# lumiere_ctrl_shematic.net
KiCad netlist of a schematic drawn in Altium Designer
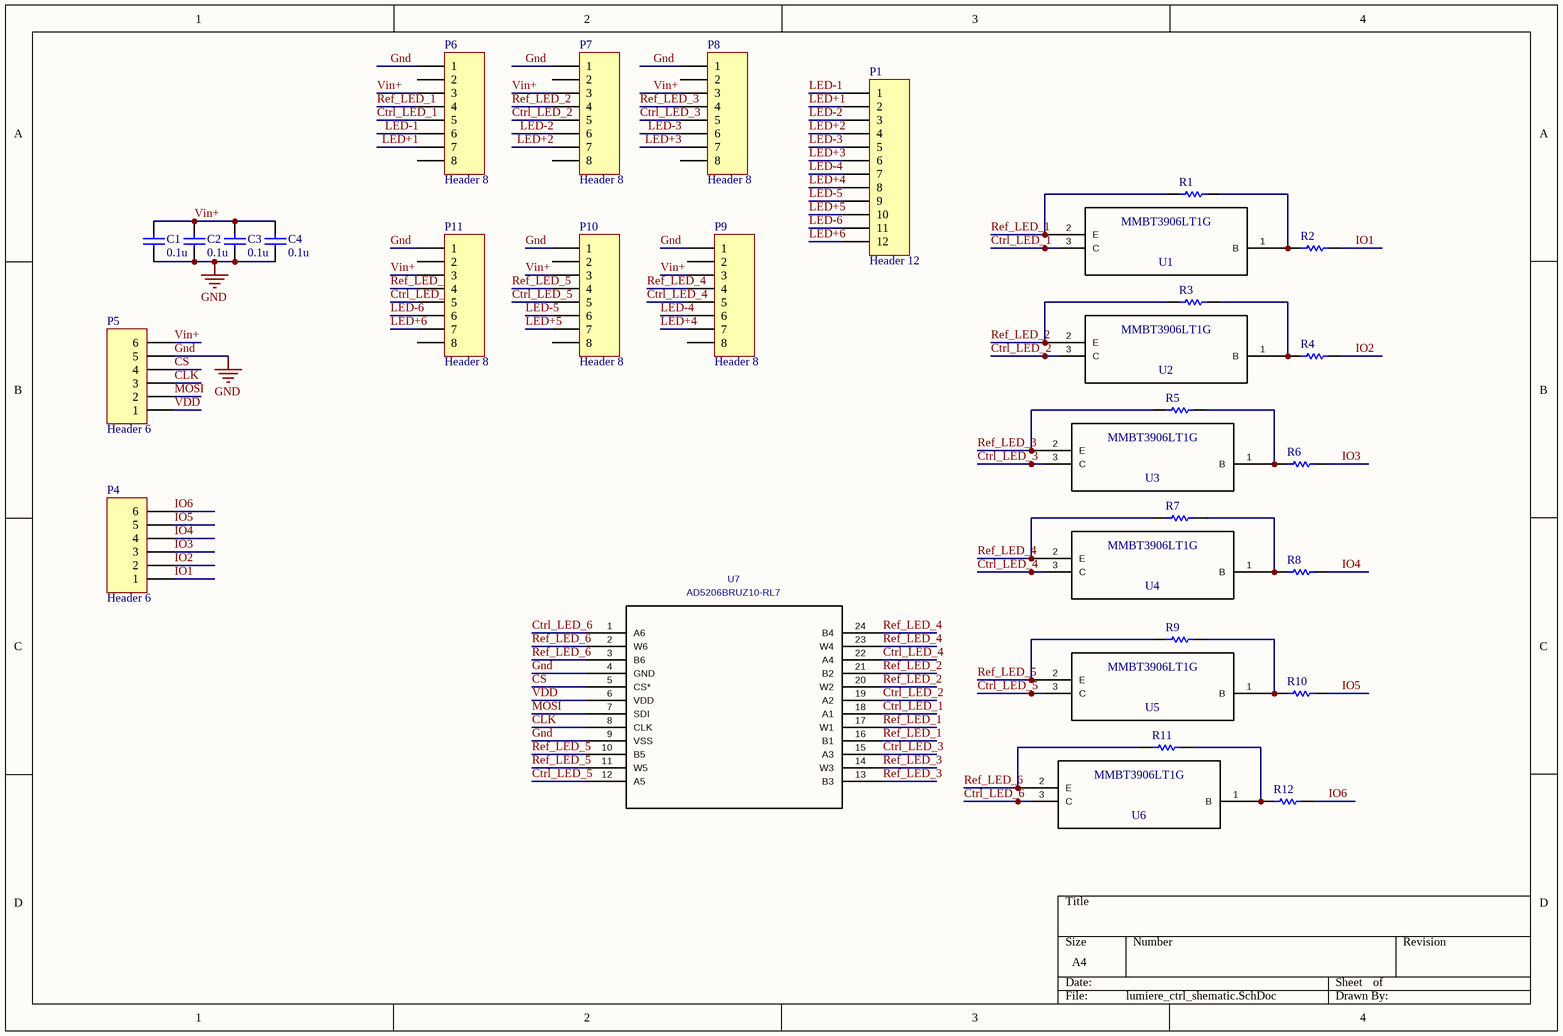
[diagram p0: lumiere_ctrl_shematic.SchDoc]

(export (version "E")
  (design (tool "Eeschema 10.0.6"))
  (components
    (comp (ref "C1")
      (value "0.1u")
      (footprint "CC1206N")
      (description "Capacitor")
      (fields (field (name "VOLTAGE") "50V") (field (name "Comment") "CapSMD"))
      (libsource (lib "S3_projet") (part "CapSMD"))
    )
    (comp (ref "C2")
      (value "0.1u")
      (footprint "CC1206N")
      (description "Capacitor")
      (fields (field (name "VOLTAGE") "50V") (field (name "Comment") "CapSMD"))
      (libsource (lib "S3_projet") (part "CapSMD"))
    )
    (comp (ref "C3")
      (value "0.1u")
      (footprint "CC1206N")
      (description "Capacitor")
      (fields (field (name "VOLTAGE") "50V") (field (name "Comment") "CapSMD"))
      (libsource (lib "S3_projet") (part "CapSMD"))
    )
    (comp (ref "C4")
      (value "0.1u")
      (footprint "CC1206N")
      (description "Capacitor")
      (fields (field (name "VOLTAGE") "50V") (field (name "Comment") "CapSMD"))
      (libsource (lib "S3_projet") (part "CapSMD"))
    )
    (comp (ref "P1")
      (value "Header 12")
      (footprint "Terminal block 12 pos")
      (description "Header, 12-Pin")
      (fields (field (name "PUBLISHER") "Altium Limited"))
      (libsource (lib "Miscellaneous Connectors") (part "Header 12"))
    )
    (comp (ref "P4")
      (value "Header 6")
      (footprint "Terminal block 6 pos")
      (description "Header, 6-Pin")
      (fields (field (name "PUBLISHER") "Altium Limited"))
      (libsource (lib "Miscellaneous Connectors") (part "Header 6"))
    )
    (comp (ref "P5")
      (value "Header 6")
      (footprint "Terminal block 6 pos")
      (description "Header, 6-Pin")
      (fields (field (name "PUBLISHER") "Altium Limited"))
      (libsource (lib "Miscellaneous Connectors") (part "Header 6"))
    )
    (comp (ref "P6")
      (value "Header 8")
      (footprint "HDR1X8")
      (description "Header, 8-Pin")
      (fields (field (name "PUBLISHER") "Altium Limited"))
      (libsource (lib "Miscellaneous Connectors") (part "Header 8"))
    )
    (comp (ref "P7")
      (value "Header 8")
      (footprint "HDR1X8")
      (description "Header, 8-Pin")
      (fields (field (name "PUBLISHER") "Altium Limited"))
      (libsource (lib "Miscellaneous Connectors") (part "Header 8"))
    )
    (comp (ref "P8")
      (value "Header 8")
      (footprint "HDR1X8")
      (description "Header, 8-Pin")
      (fields (field (name "PUBLISHER") "Altium Limited"))
      (libsource (lib "Miscellaneous Connectors") (part "Header 8"))
    )
    (comp (ref "P9")
      (value "Header 8")
      (footprint "HDR1X8")
      (description "Header, 8-Pin")
      (fields (field (name "PUBLISHER") "Altium Limited"))
      (libsource (lib "Miscellaneous Connectors") (part "Header 8"))
    )
    (comp (ref "P10")
      (value "Header 8")
      (footprint "HDR1X8")
      (description "Header, 8-Pin")
      (fields (field (name "PUBLISHER") "Altium Limited"))
      (libsource (lib "Miscellaneous Connectors") (part "Header 8"))
    )
    (comp (ref "P11")
      (value "Header 8")
      (footprint "HDR1X8")
      (description "Header, 8-Pin")
      (fields (field (name "PUBLISHER") "Altium Limited"))
      (libsource (lib "Miscellaneous Connectors") (part "Header 8"))
    )
    (comp (ref "R1")
      (value "ResSMD")
      (footprint "STA_RMCF1206")
      (libsource (lib "S3_projet") (part "ResSMD"))
    )
    (comp (ref "R2")
      (value "ResSMD")
      (footprint "STA_RMCF1206")
      (libsource (lib "S3_projet") (part "ResSMD"))
    )
    (comp (ref "R3")
      (value "ResSMD")
      (footprint "STA_RMCF1206")
      (libsource (lib "S3_projet") (part "ResSMD"))
    )
    (comp (ref "R4")
      (value "ResSMD")
      (footprint "STA_RMCF1206")
      (libsource (lib "S3_projet") (part "ResSMD"))
    )
    (comp (ref "R5")
      (value "ResSMD")
      (footprint "STA_RMCF1206")
      (libsource (lib "S3_projet") (part "ResSMD"))
    )
    (comp (ref "R6")
      (value "ResSMD")
      (footprint "STA_RMCF1206")
      (libsource (lib "S3_projet") (part "ResSMD"))
    )
    (comp (ref "R7")
      (value "ResSMD")
      (footprint "STA_RMCF1206")
      (libsource (lib "S3_projet") (part "ResSMD"))
    )
    (comp (ref "R8")
      (value "ResSMD")
      (footprint "STA_RMCF1206")
      (libsource (lib "S3_projet") (part "ResSMD"))
    )
    (comp (ref "R9")
      (value "ResSMD")
      (footprint "STA_RMCF1206")
      (libsource (lib "S3_projet") (part "ResSMD"))
    )
    (comp (ref "R10")
      (value "ResSMD")
      (footprint "STA_RMCF1206")
      (libsource (lib "S3_projet") (part "ResSMD"))
    )
    (comp (ref "R11")
      (value "ResSMD")
      (footprint "STA_RMCF1206")
      (libsource (lib "S3_projet") (part "ResSMD"))
    )
    (comp (ref "R12")
      (value "ResSMD")
      (footprint "STA_RMCF1206")
      (libsource (lib "S3_projet") (part "ResSMD"))
    )
    (comp (ref "U1")
      (value "MMBT3906LT1G")
      (footprint "SOT-23")
      (libsource (lib "AltiumV15") (part "MMBT3906LT1G"))
    )
    (comp (ref "U2")
      (value "MMBT3906LT1G")
      (footprint "SOT-23")
      (libsource (lib "AltiumV15") (part "MMBT3906LT1G"))
    )
    (comp (ref "U3")
      (value "MMBT3906LT1G")
      (footprint "SOT-23")
      (libsource (lib "AltiumV15") (part "MMBT3906LT1G"))
    )
    (comp (ref "U4")
      (value "MMBT3906LT1G")
      (footprint "SOT-23")
      (libsource (lib "AltiumV15") (part "MMBT3906LT1G"))
    )
    (comp (ref "U5")
      (value "MMBT3906LT1G")
      (footprint "SOT-23")
      (libsource (lib "AltiumV15") (part "MMBT3906LT1G"))
    )
    (comp (ref "U6")
      (value "MMBT3906LT1G")
      (footprint "SOT-23")
      (libsource (lib "AltiumV15") (part "MMBT3906LT1G"))
    )
    (comp (ref "U7")
      (value "AD5206BRUZ10-RL7")
      (footprint "RU_24")
      (libsource (lib "AltiumV15") (part "AD5206BRUZ10-RL7"))
    )
  )
  (nets
    (net (code "1") (name "/CLK") (class "Default")
      (node (ref "P5") (pin "3") (pinfunction "3_3") (pintype "passive"))
      (node (ref "U7") (pin "8") (pinfunction "CLK_8") (pintype "passive"))
    )
    (net (code "2") (name "/CS") (class "Default")
      (node (ref "P5") (pin "4") (pinfunction "4_4") (pintype "passive"))
      (node (ref "U7") (pin "5") (pinfunction "CS*_5") (pintype "passive"))
    )
    (net (code "3") (name "/Ctrl_LED_1") (class "Default")
      (node (ref "P6") (pin "5") (pinfunction "5_5") (pintype "passive"))
      (node (ref "U1") (pin "3") (pinfunction "C_3") (pintype "passive"))
      (node (ref "U7") (pin "18") (pinfunction "A1_18") (pintype "passive"))
    )
    (net (code "4") (name "/Ctrl_LED_2") (class "Default")
      (node (ref "P7") (pin "5") (pinfunction "5_5") (pintype "passive"))
      (node (ref "U2") (pin "3") (pinfunction "C_3") (pintype "passive"))
      (node (ref "U7") (pin "19") (pinfunction "A2_19") (pintype "passive"))
    )
    (net (code "5") (name "/Ctrl_LED_3") (class "Default")
      (node (ref "P8") (pin "5") (pinfunction "5_5") (pintype "passive"))
      (node (ref "U3") (pin "3") (pinfunction "C_3") (pintype "passive"))
      (node (ref "U7") (pin "15") (pinfunction "A3_15") (pintype "passive"))
    )
    (net (code "6") (name "/Ctrl_LED_4") (class "Default")
      (node (ref "P9") (pin "5") (pinfunction "5_5") (pintype "passive"))
      (node (ref "U4") (pin "3") (pinfunction "C_3") (pintype "passive"))
      (node (ref "U7") (pin "22") (pinfunction "A4_22") (pintype "passive"))
    )
    (net (code "7") (name "/Ctrl_LED_5") (class "Default")
      (node (ref "P10") (pin "5") (pinfunction "5_5") (pintype "passive"))
      (node (ref "U5") (pin "3") (pinfunction "C_3") (pintype "passive"))
      (node (ref "U7") (pin "12") (pinfunction "A5_12") (pintype "passive"))
    )
    (net (code "8") (name "/Ctrl_LED_6") (class "Default")
      (node (ref "P11") (pin "5") (pinfunction "5_5") (pintype "passive"))
      (node (ref "U6") (pin "3") (pinfunction "C_3") (pintype "passive"))
      (node (ref "U7") (pin "1") (pinfunction "A6_1") (pintype "passive"))
    )
    (net (code "9") (name "/IO1") (class "Default")
      (node (ref "P4") (pin "1") (pinfunction "1_1") (pintype "passive"))
      (node (ref "R2") (pin "1") (pinfunction "1_1") (pintype "passive"))
    )
    (net (code "10") (name "/IO2") (class "Default")
      (node (ref "P4") (pin "2") (pinfunction "2_2") (pintype "passive"))
      (node (ref "R4") (pin "1") (pinfunction "1_1") (pintype "passive"))
    )
    (net (code "11") (name "/IO3") (class "Default")
      (node (ref "P4") (pin "3") (pinfunction "3_3") (pintype "passive"))
      (node (ref "R6") (pin "1") (pinfunction "1_1") (pintype "passive"))
    )
    (net (code "12") (name "/IO4") (class "Default")
      (node (ref "P4") (pin "4") (pinfunction "4_4") (pintype "passive"))
      (node (ref "R8") (pin "1") (pinfunction "1_1") (pintype "passive"))
    )
    (net (code "13") (name "/IO5") (class "Default")
      (node (ref "P4") (pin "5") (pinfunction "5_5") (pintype "passive"))
      (node (ref "R10") (pin "1") (pinfunction "1_1") (pintype "passive"))
    )
    (net (code "14") (name "/IO6") (class "Default")
      (node (ref "P4") (pin "6") (pinfunction "6_6") (pintype "passive"))
      (node (ref "R12") (pin "1") (pinfunction "1_1") (pintype "passive"))
    )
    (net (code "15") (name "/LED+1") (class "Default")
      (node (ref "P1") (pin "2") (pinfunction "2_2") (pintype "passive"))
      (node (ref "P6") (pin "7") (pinfunction "7_7") (pintype "passive"))
    )
    (net (code "16") (name "/LED+2") (class "Default")
      (node (ref "P1") (pin "4") (pinfunction "4_4") (pintype "passive"))
      (node (ref "P7") (pin "7") (pinfunction "7_7") (pintype "passive"))
    )
    (net (code "17") (name "/LED+3") (class "Default")
      (node (ref "P1") (pin "6") (pinfunction "6_6") (pintype "passive"))
      (node (ref "P8") (pin "7") (pinfunction "7_7") (pintype "passive"))
    )
    (net (code "18") (name "/LED+4") (class "Default")
      (node (ref "P1") (pin "8") (pinfunction "8_8") (pintype "passive"))
      (node (ref "P9") (pin "7") (pinfunction "7_7") (pintype "passive"))
    )
    (net (code "19") (name "/LED+5") (class "Default")
      (node (ref "P1") (pin "10") (pinfunction "10_10") (pintype "passive"))
      (node (ref "P10") (pin "7") (pinfunction "7_7") (pintype "passive"))
    )
    (net (code "20") (name "/LED+6") (class "Default")
      (node (ref "P1") (pin "12") (pinfunction "12_12") (pintype "passive"))
      (node (ref "P11") (pin "7") (pinfunction "7_7") (pintype "passive"))
    )
    (net (code "21") (name "/LED-1") (class "Default")
      (node (ref "P1") (pin "1") (pinfunction "1_1") (pintype "passive"))
      (node (ref "P6") (pin "6") (pinfunction "6_6") (pintype "passive"))
    )
    (net (code "22") (name "/LED-2") (class "Default")
      (node (ref "P1") (pin "3") (pinfunction "3_3") (pintype "passive"))
      (node (ref "P7") (pin "6") (pinfunction "6_6") (pintype "passive"))
    )
    (net (code "23") (name "/LED-3") (class "Default")
      (node (ref "P1") (pin "5") (pinfunction "5_5") (pintype "passive"))
      (node (ref "P8") (pin "6") (pinfunction "6_6") (pintype "passive"))
    )
    (net (code "24") (name "/LED-4") (class "Default")
      (node (ref "P1") (pin "7") (pinfunction "7_7") (pintype "passive"))
      (node (ref "P9") (pin "6") (pinfunction "6_6") (pintype "passive"))
    )
    (net (code "25") (name "/LED-5") (class "Default")
      (node (ref "P1") (pin "9") (pinfunction "9_9") (pintype "passive"))
      (node (ref "P10") (pin "6") (pinfunction "6_6") (pintype "passive"))
    )
    (net (code "26") (name "/LED-6") (class "Default")
      (node (ref "P1") (pin "11") (pinfunction "11_11") (pintype "passive"))
      (node (ref "P11") (pin "6") (pinfunction "6_6") (pintype "passive"))
    )
    (net (code "27") (name "/MOSI") (class "Default")
      (node (ref "P5") (pin "2") (pinfunction "2_2") (pintype "passive"))
      (node (ref "U7") (pin "7") (pinfunction "SDI_7") (pintype "passive"))
    )
    (net (code "28") (name "/Ref_LED_1") (class "Default")
      (node (ref "P6") (pin "4") (pinfunction "4_4") (pintype "passive"))
      (node (ref "R1") (pin "2") (pinfunction "2_2") (pintype "passive"))
      (node (ref "U1") (pin "2") (pinfunction "E_2") (pintype "passive"))
      (node (ref "U7") (pin "16") (pinfunction "B1_16") (pintype "passive"))
      (node (ref "U7") (pin "17") (pinfunction "W1_17") (pintype "passive"))
    )
    (net (code "29") (name "/Ref_LED_2") (class "Default")
      (node (ref "P7") (pin "4") (pinfunction "4_4") (pintype "passive"))
      (node (ref "R3") (pin "2") (pinfunction "2_2") (pintype "passive"))
      (node (ref "U2") (pin "2") (pinfunction "E_2") (pintype "passive"))
      (node (ref "U7") (pin "20") (pinfunction "W2_20") (pintype "passive"))
      (node (ref "U7") (pin "21") (pinfunction "B2_21") (pintype "passive"))
    )
    (net (code "30") (name "/Ref_LED_3") (class "Default")
      (node (ref "P8") (pin "4") (pinfunction "4_4") (pintype "passive"))
      (node (ref "R5") (pin "2") (pinfunction "2_2") (pintype "passive"))
      (node (ref "U3") (pin "2") (pinfunction "E_2") (pintype "passive"))
      (node (ref "U7") (pin "13") (pinfunction "B3_13") (pintype "passive"))
      (node (ref "U7") (pin "14") (pinfunction "W3_14") (pintype "passive"))
    )
    (net (code "31") (name "/Ref_LED_4") (class "Default")
      (node (ref "P9") (pin "4") (pinfunction "4_4") (pintype "passive"))
      (node (ref "R7") (pin "2") (pinfunction "2_2") (pintype "passive"))
      (node (ref "U4") (pin "2") (pinfunction "E_2") (pintype "passive"))
      (node (ref "U7") (pin "23") (pinfunction "W4_23") (pintype "passive"))
      (node (ref "U7") (pin "24") (pinfunction "B4_24") (pintype "passive"))
    )
    (net (code "32") (name "/Ref_LED_5") (class "Default")
      (node (ref "P10") (pin "4") (pinfunction "4_4") (pintype "passive"))
      (node (ref "R9") (pin "2") (pinfunction "2_2") (pintype "passive"))
      (node (ref "U5") (pin "2") (pinfunction "E_2") (pintype "passive"))
      (node (ref "U7") (pin "10") (pinfunction "B5_10") (pintype "passive"))
      (node (ref "U7") (pin "11") (pinfunction "W5_11") (pintype "passive"))
    )
    (net (code "33") (name "/Ref_LED_6") (class "Default")
      (node (ref "P11") (pin "4") (pinfunction "4_4") (pintype "passive"))
      (node (ref "R11") (pin "2") (pinfunction "2_2") (pintype "passive"))
      (node (ref "U6") (pin "2") (pinfunction "E_2") (pintype "passive"))
      (node (ref "U7") (pin "2") (pinfunction "W6_2") (pintype "passive"))
      (node (ref "U7") (pin "3") (pinfunction "B6_3") (pintype "passive"))
    )
    (net (code "34") (name "/VDD") (class "Default")
      (node (ref "P5") (pin "1") (pinfunction "1_1") (pintype "passive"))
      (node (ref "U7") (pin "6") (pinfunction "VDD_6") (pintype "power_in"))
    )
    (net (code "35") (name "/Vin+") (class "Default")
      (node (ref "C1") (pin "2") (pinfunction "2_2") (pintype "passive"))
      (node (ref "C2") (pin "2") (pinfunction "2_2") (pintype "passive"))
      (node (ref "C3") (pin "2") (pinfunction "2_2") (pintype "passive"))
      (node (ref "C4") (pin "2") (pinfunction "2_2") (pintype "passive"))
      (node (ref "P10") (pin "3") (pinfunction "3_3") (pintype "passive"))
      (node (ref "P11") (pin "3") (pinfunction "3_3") (pintype "passive"))
      (node (ref "P5") (pin "6") (pinfunction "6_6") (pintype "passive"))
      (node (ref "P6") (pin "3") (pinfunction "3_3") (pintype "passive"))
      (node (ref "P7") (pin "3") (pinfunction "3_3") (pintype "passive"))
      (node (ref "P8") (pin "3") (pinfunction "3_3") (pintype "passive"))
      (node (ref "P9") (pin "3") (pinfunction "3_3") (pintype "passive"))
    )
    (net (code "36") (name "GND") (class "Default")
      (node (ref "C1") (pin "1") (pinfunction "1_1") (pintype "passive"))
      (node (ref "C2") (pin "1") (pinfunction "1_1") (pintype "passive"))
      (node (ref "C3") (pin "1") (pinfunction "1_1") (pintype "passive"))
      (node (ref "C4") (pin "1") (pinfunction "1_1") (pintype "passive"))
      (node (ref "P10") (pin "1") (pinfunction "1_1") (pintype "passive"))
      (node (ref "P11") (pin "1") (pinfunction "1_1") (pintype "passive"))
      (node (ref "P5") (pin "5") (pinfunction "5_5") (pintype "passive"))
      (node (ref "P6") (pin "1") (pinfunction "1_1") (pintype "passive"))
      (node (ref "P7") (pin "1") (pinfunction "1_1") (pintype "passive"))
      (node (ref "P8") (pin "1") (pinfunction "1_1") (pintype "passive"))
      (node (ref "P9") (pin "1") (pinfunction "1_1") (pintype "passive"))
      (node (ref "U7") (pin "4") (pinfunction "GND_4") (pintype "passive"))
      (node (ref "U7") (pin "9") (pinfunction "VSS_9") (pintype "power_in"))
    )
    (net (code "37") (name "Net-(U1-B)") (class "Default")
      (node (ref "R1") (pin "1") (pinfunction "1_1") (pintype "passive"))
      (node (ref "R2") (pin "2") (pinfunction "2_2") (pintype "passive"))
      (node (ref "U1") (pin "1") (pinfunction "B_1") (pintype "passive"))
    )
    (net (code "38") (name "Net-(U2-B)") (class "Default")
      (node (ref "R3") (pin "1") (pinfunction "1_1") (pintype "passive"))
      (node (ref "R4") (pin "2") (pinfunction "2_2") (pintype "passive"))
      (node (ref "U2") (pin "1") (pinfunction "B_1") (pintype "passive"))
    )
    (net (code "39") (name "Net-(U3-B)") (class "Default")
      (node (ref "R5") (pin "1") (pinfunction "1_1") (pintype "passive"))
      (node (ref "R6") (pin "2") (pinfunction "2_2") (pintype "passive"))
      (node (ref "U3") (pin "1") (pinfunction "B_1") (pintype "passive"))
    )
    (net (code "40") (name "Net-(U4-B)") (class "Default")
      (node (ref "R7") (pin "1") (pinfunction "1_1") (pintype "passive"))
      (node (ref "R8") (pin "2") (pinfunction "2_2") (pintype "passive"))
      (node (ref "U4") (pin "1") (pinfunction "B_1") (pintype "passive"))
    )
    (net (code "41") (name "Net-(U5-B)") (class "Default")
      (node (ref "R10") (pin "2") (pinfunction "2_2") (pintype "passive"))
      (node (ref "R9") (pin "1") (pinfunction "1_1") (pintype "passive"))
      (node (ref "U5") (pin "1") (pinfunction "B_1") (pintype "passive"))
    )
    (net (code "42") (name "Net-(U6-B)") (class "Default")
      (node (ref "R11") (pin "1") (pinfunction "1_1") (pintype "passive"))
      (node (ref "R12") (pin "2") (pinfunction "2_2") (pintype "passive"))
      (node (ref "U6") (pin "1") (pinfunction "B_1") (pintype "passive"))
    )
    (net (code "43") (name "unconnected-(P6-Pad2)") (class "Default")
      (node (ref "P6") (pin "2") (pinfunction "2_2") (pintype "passive"))
    )
    (net (code "44") (name "unconnected-(P6-Pad8)") (class "Default")
      (node (ref "P6") (pin "8") (pinfunction "8_8") (pintype "passive"))
    )
    (net (code "45") (name "unconnected-(P7-Pad2)") (class "Default")
      (node (ref "P7") (pin "2") (pinfunction "2_2") (pintype "passive"))
    )
    (net (code "46") (name "unconnected-(P7-Pad8)") (class "Default")
      (node (ref "P7") (pin "8") (pinfunction "8_8") (pintype "passive"))
    )
    (net (code "47") (name "unconnected-(P8-Pad2)") (class "Default")
      (node (ref "P8") (pin "2") (pinfunction "2_2") (pintype "passive"))
    )
    (net (code "48") (name "unconnected-(P8-Pad8)") (class "Default")
      (node (ref "P8") (pin "8") (pinfunction "8_8") (pintype "passive"))
    )
    (net (code "49") (name "unconnected-(P9-Pad2)") (class "Default")
      (node (ref "P9") (pin "2") (pinfunction "2_2") (pintype "passive"))
    )
    (net (code "50") (name "unconnected-(P9-Pad8)") (class "Default")
      (node (ref "P9") (pin "8") (pinfunction "8_8") (pintype "passive"))
    )
    (net (code "51") (name "unconnected-(P10-Pad2)") (class "Default")
      (node (ref "P10") (pin "2") (pinfunction "2_2") (pintype "passive"))
    )
    (net (code "52") (name "unconnected-(P10-Pad8)") (class "Default")
      (node (ref "P10") (pin "8") (pinfunction "8_8") (pintype "passive"))
    )
    (net (code "53") (name "unconnected-(P11-Pad2)") (class "Default")
      (node (ref "P11") (pin "2") (pinfunction "2_2") (pintype "passive"))
    )
    (net (code "54") (name "unconnected-(P11-Pad8)") (class "Default")
      (node (ref "P11") (pin "8") (pinfunction "8_8") (pintype "passive"))
    )
  )
)
